# feelerBox1.net
KiCad netlist of a schematic drawn in EAGLE
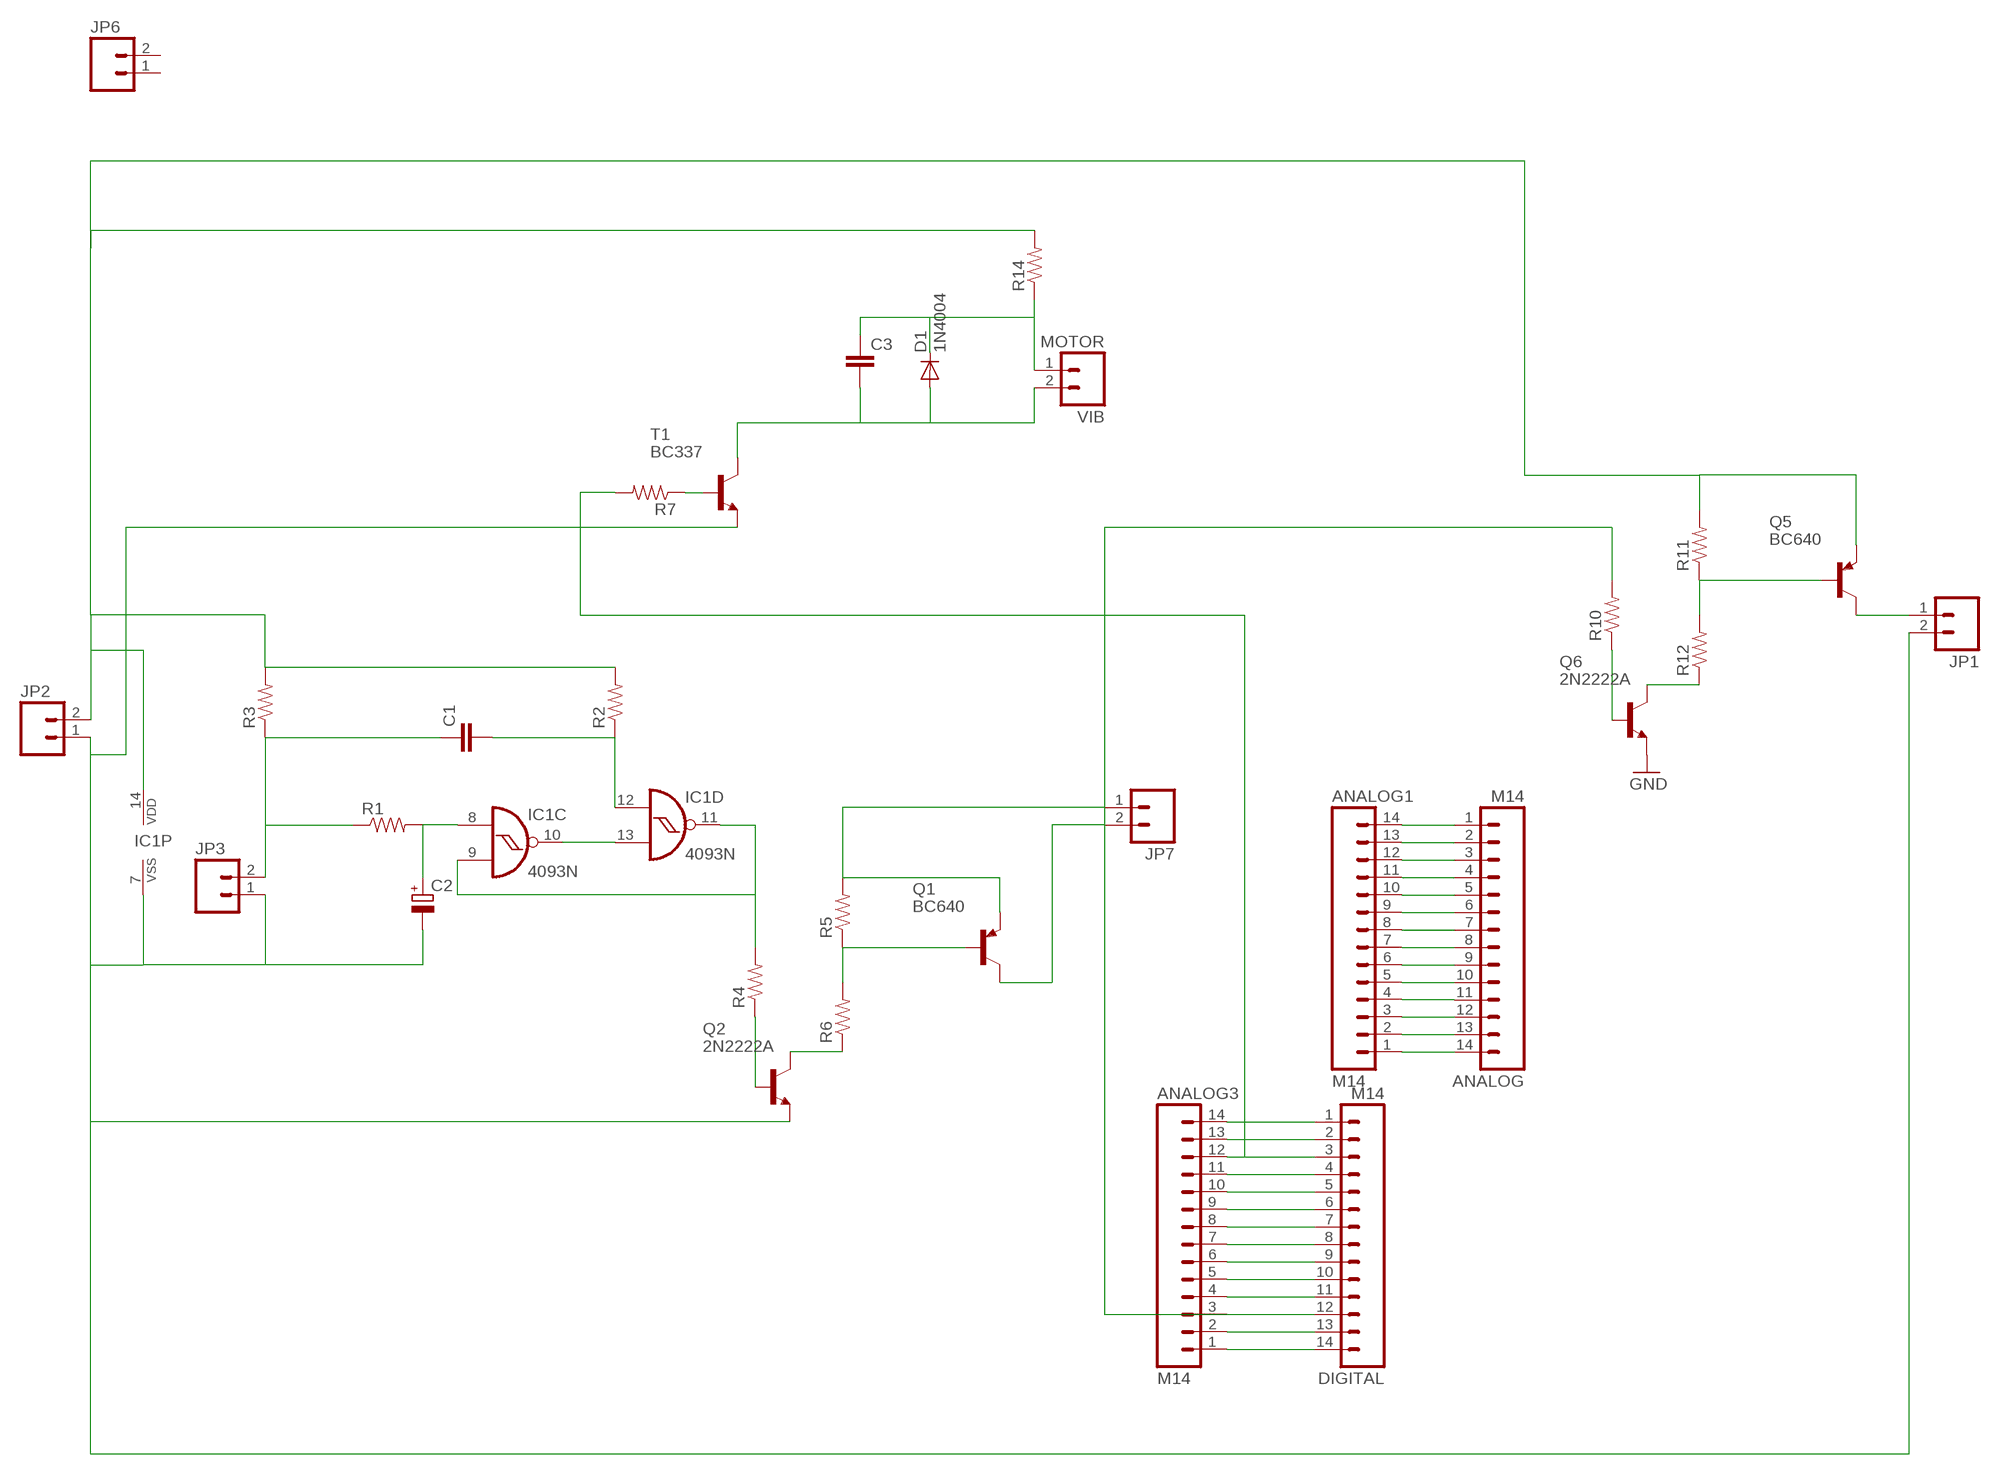
[diagram p0: schematic, sheet 1]

(export (version "E")
  (design (tool "Eeschema 10.0.6"))
  (components
    (comp (ref "ANALOG")
      (value "M14")
      (footprint "eagle-import:1X14")
      (libsource (lib "eagle-import") (part "M14"))
    )
    (comp (ref "ANALOG1")
      (value "M14")
      (footprint "eagle-import:1X14")
      (libsource (lib "eagle-import") (part "M14"))
    )
    (comp (ref "ANALOG3")
      (value "M14")
      (footprint "eagle-import:1X14")
      (libsource (lib "eagle-import") (part "M14"))
    )
    (comp (ref "C1")
      (value "0.1UF-50V-20%(PTH)KIT-EZ")
      (footprint "eagle-import:CAP-PTH-SMALL-KIT")
      (libsource (lib "eagle-import") (part "0.1UF-50V-20%(PTH)KIT-EZ"))
    )
    (comp (ref "C2")
      (value "CPOL-EUE2.5-5")
      (footprint "eagle-import:E2,5-5")
      (libsource (lib "eagle-import") (part "CPOL-EUE2.5-5"))
    )
    (comp (ref "C3")
      (value "CAPKIT")
      (footprint "eagle-import:CAP-PTH-SMALL-KIT")
      (libsource (lib "eagle-import") (part "CAPKIT"))
    )
    (comp (ref "D1")
      (value "1N4004")
      (footprint "eagle-import:DO41-10")
      (libsource (lib "eagle-import") (part "1N4004"))
    )
    (comp (ref "DIGITAL")
      (value "M14")
      (footprint "eagle-import:1X14")
      (libsource (lib "eagle-import") (part "M14"))
    )
    (comp (ref "IC1")
      (value "4093N")
      (footprint "eagle-import:DIL14")
      (libsource (lib "eagle-import") (part "4093N"))
    )
    (comp (ref "JP1")
      (value "M02PTH")
      (footprint "eagle-import:1X02")
      (libsource (lib "eagle-import") (part "M02PTH"))
    )
    (comp (ref "JP2")
      (value "M02PTH")
      (footprint "eagle-import:1X02")
      (libsource (lib "eagle-import") (part "M02PTH"))
    )
    (comp (ref "JP3")
      (value "M02PTH")
      (footprint "eagle-import:1X02")
      (libsource (lib "eagle-import") (part "M02PTH"))
    )
    (comp (ref "JP6")
      (value "M02PTH")
      (footprint "eagle-import:1X02")
      (libsource (lib "eagle-import") (part "M02PTH"))
    )
    (comp (ref "JP7")
      (value "M02PTH")
      (footprint "eagle-import:1X02")
      (libsource (lib "eagle-import") (part "M02PTH"))
    )
    (comp (ref "Q1")
      (value "BC640")
      (footprint "eagle-import:TO92-BCE")
      (libsource (lib "eagle-import") (part "BC640"))
    )
    (comp (ref "Q2")
      (value "2N2222A")
      (footprint "eagle-import:TO18")
      (libsource (lib "eagle-import") (part "2N2222A"))
    )
    (comp (ref "Q5")
      (value "BC640")
      (footprint "eagle-import:TO92-BCE")
      (libsource (lib "eagle-import") (part "BC640"))
    )
    (comp (ref "Q6")
      (value "2N2222A")
      (footprint "eagle-import:TO18")
      (libsource (lib "eagle-import") (part "2N2222A"))
    )
    (comp (ref "R1")
      (value "RESISTORAXIAL-0.3")
      (footprint "eagle-import:AXIAL-0.3")
      (libsource (lib "eagle-import") (part "RESISTORAXIAL-0.3"))
    )
    (comp (ref "R2")
      (value "RESISTORAXIAL-0.3")
      (footprint "eagle-import:AXIAL-0.3")
      (libsource (lib "eagle-import") (part "RESISTORAXIAL-0.3"))
    )
    (comp (ref "R3")
      (value "RESISTORAXIAL-0.3")
      (footprint "eagle-import:AXIAL-0.3")
      (libsource (lib "eagle-import") (part "RESISTORAXIAL-0.3"))
    )
    (comp (ref "R4")
      (value "RESISTORPTH-1/4W-VERT")
      (footprint "eagle-import:AXIAL-0.1")
      (libsource (lib "eagle-import") (part "RESISTORPTH-1/4W-VERT"))
    )
    (comp (ref "R5")
      (value "RESISTORPTH-1/4W-VERT")
      (footprint "eagle-import:AXIAL-0.1")
      (libsource (lib "eagle-import") (part "RESISTORPTH-1/4W-VERT"))
    )
    (comp (ref "R6")
      (value "RESISTORPTH-1/4W-VERT")
      (footprint "eagle-import:AXIAL-0.1")
      (libsource (lib "eagle-import") (part "RESISTORPTH-1/4W-VERT"))
    )
    (comp (ref "R7")
      (value "RESISTORAXIAL-0.3")
      (footprint "eagle-import:AXIAL-0.3")
      (libsource (lib "eagle-import") (part "RESISTORAXIAL-0.3"))
    )
    (comp (ref "R10")
      (value "RESISTORPTH-1/4W-VERT")
      (footprint "eagle-import:AXIAL-0.1")
      (libsource (lib "eagle-import") (part "RESISTORPTH-1/4W-VERT"))
    )
    (comp (ref "R11")
      (value "RESISTORPTH-1/4W-VERT")
      (footprint "eagle-import:AXIAL-0.1")
      (libsource (lib "eagle-import") (part "RESISTORPTH-1/4W-VERT"))
    )
    (comp (ref "R12")
      (value "RESISTORPTH-1/4W-VERT")
      (footprint "eagle-import:AXIAL-0.1")
      (libsource (lib "eagle-import") (part "RESISTORPTH-1/4W-VERT"))
    )
    (comp (ref "R14")
      (value "RESISTORPTH-1/4W-VERT")
      (footprint "eagle-import:AXIAL-0.1")
      (libsource (lib "eagle-import") (part "RESISTORPTH-1/4W-VERT"))
    )
    (comp (ref "T1")
      (value "BC337")
      (footprint "eagle-import:TO92")
      (libsource (lib "eagle-import") (part "BC337"))
    )
    (comp (ref "VIB")
      (value "MOTOR")
      (footprint "eagle-import:1X02")
      (libsource (lib "eagle-import") (part "M02PTH"))
    )
  )
  (nets
    (net (code "1") (name "GND") (class "Default")
      (node (ref "ANALOG3") (pin "13") (pinfunction "13_13") (pintype "passive"))
      (node (ref "DIGITAL") (pin "2") (pinfunction "2_2") (pintype "passive"))
      (node (ref "Q6") (pin "1") (pinfunction "E_1") (pintype "passive"))
    )
    (net (code "2") (name "Net-(ANALOG-Pad1)") (class "Default")
      (node (ref "ANALOG") (pin "1") (pinfunction "1_1") (pintype "passive"))
      (node (ref "ANALOG1") (pin "14") (pinfunction "14_14") (pintype "passive"))
    )
    (net (code "3") (name "Net-(ANALOG-Pad2)") (class "Default")
      (node (ref "ANALOG") (pin "2") (pinfunction "2_2") (pintype "passive"))
      (node (ref "ANALOG1") (pin "13") (pinfunction "13_13") (pintype "passive"))
    )
    (net (code "4") (name "Net-(ANALOG-Pad3)") (class "Default")
      (node (ref "ANALOG") (pin "3") (pinfunction "3_3") (pintype "passive"))
      (node (ref "ANALOG1") (pin "12") (pinfunction "12_12") (pintype "passive"))
    )
    (net (code "5") (name "Net-(ANALOG-Pad4)") (class "Default")
      (node (ref "ANALOG") (pin "4") (pinfunction "4_4") (pintype "passive"))
      (node (ref "ANALOG1") (pin "11") (pinfunction "11_11") (pintype "passive"))
    )
    (net (code "6") (name "Net-(ANALOG-Pad5)") (class "Default")
      (node (ref "ANALOG") (pin "5") (pinfunction "5_5") (pintype "passive"))
      (node (ref "ANALOG1") (pin "10") (pinfunction "10_10") (pintype "passive"))
    )
    (net (code "7") (name "Net-(ANALOG-Pad6)") (class "Default")
      (node (ref "ANALOG") (pin "6") (pinfunction "6_6") (pintype "passive"))
      (node (ref "ANALOG1") (pin "9") (pinfunction "9_9") (pintype "passive"))
    )
    (net (code "8") (name "Net-(ANALOG-Pad7)") (class "Default")
      (node (ref "ANALOG") (pin "7") (pinfunction "7_7") (pintype "passive"))
      (node (ref "ANALOG1") (pin "8") (pinfunction "8_8") (pintype "passive"))
    )
    (net (code "9") (name "Net-(ANALOG-Pad8)") (class "Default")
      (node (ref "ANALOG") (pin "8") (pinfunction "8_8") (pintype "passive"))
      (node (ref "ANALOG1") (pin "7") (pinfunction "7_7") (pintype "passive"))
    )
    (net (code "10") (name "Net-(ANALOG-Pad9)") (class "Default")
      (node (ref "ANALOG") (pin "9") (pinfunction "9_9") (pintype "passive"))
      (node (ref "ANALOG1") (pin "6") (pinfunction "6_6") (pintype "passive"))
    )
    (net (code "11") (name "Net-(ANALOG-Pad10)") (class "Default")
      (node (ref "ANALOG") (pin "10") (pinfunction "10_10") (pintype "passive"))
      (node (ref "ANALOG1") (pin "5") (pinfunction "5_5") (pintype "passive"))
    )
    (net (code "12") (name "Net-(ANALOG-Pad11)") (class "Default")
      (node (ref "ANALOG") (pin "11") (pinfunction "11_11") (pintype "passive"))
      (node (ref "ANALOG1") (pin "4") (pinfunction "4_4") (pintype "passive"))
    )
    (net (code "13") (name "Net-(ANALOG-Pad12)") (class "Default")
      (node (ref "ANALOG") (pin "12") (pinfunction "12_12") (pintype "passive"))
      (node (ref "ANALOG1") (pin "3") (pinfunction "3_3") (pintype "passive"))
    )
    (net (code "14") (name "Net-(ANALOG-Pad13)") (class "Default")
      (node (ref "ANALOG") (pin "13") (pinfunction "13_13") (pintype "passive"))
      (node (ref "ANALOG1") (pin "2") (pinfunction "2_2") (pintype "passive"))
    )
    (net (code "15") (name "Net-(ANALOG-Pad14)") (class "Default")
      (node (ref "ANALOG") (pin "14") (pinfunction "14_14") (pintype "passive"))
      (node (ref "ANALOG1") (pin "1") (pinfunction "1_1") (pintype "passive"))
    )
    (net (code "16") (name "Net-(ANALOG3-Pad1)") (class "Default")
      (node (ref "ANALOG3") (pin "1") (pinfunction "1_1") (pintype "passive"))
      (node (ref "DIGITAL") (pin "14") (pinfunction "14_14") (pintype "passive"))
    )
    (net (code "17") (name "Net-(ANALOG3-Pad2)") (class "Default")
      (node (ref "ANALOG3") (pin "2") (pinfunction "2_2") (pintype "passive"))
      (node (ref "DIGITAL") (pin "13") (pinfunction "13_13") (pintype "passive"))
    )
    (net (code "18") (name "Net-(ANALOG3-Pad4)") (class "Default")
      (node (ref "ANALOG3") (pin "4") (pinfunction "4_4") (pintype "passive"))
      (node (ref "DIGITAL") (pin "11") (pinfunction "11_11") (pintype "passive"))
    )
    (net (code "19") (name "Net-(ANALOG3-Pad5)") (class "Default")
      (node (ref "ANALOG3") (pin "5") (pinfunction "5_5") (pintype "passive"))
      (node (ref "DIGITAL") (pin "10") (pinfunction "10_10") (pintype "passive"))
    )
    (net (code "20") (name "Net-(ANALOG3-Pad6)") (class "Default")
      (node (ref "ANALOG3") (pin "6") (pinfunction "6_6") (pintype "passive"))
      (node (ref "DIGITAL") (pin "9") (pinfunction "9_9") (pintype "passive"))
    )
    (net (code "21") (name "Net-(ANALOG3-Pad7)") (class "Default")
      (node (ref "ANALOG3") (pin "7") (pinfunction "7_7") (pintype "passive"))
      (node (ref "DIGITAL") (pin "8") (pinfunction "8_8") (pintype "passive"))
    )
    (net (code "22") (name "Net-(ANALOG3-Pad8)") (class "Default")
      (node (ref "ANALOG3") (pin "8") (pinfunction "8_8") (pintype "passive"))
      (node (ref "DIGITAL") (pin "7") (pinfunction "7_7") (pintype "passive"))
    )
    (net (code "23") (name "Net-(ANALOG3-Pad9)") (class "Default")
      (node (ref "ANALOG3") (pin "9") (pinfunction "9_9") (pintype "passive"))
      (node (ref "DIGITAL") (pin "6") (pinfunction "6_6") (pintype "passive"))
    )
    (net (code "24") (name "Net-(ANALOG3-Pad10)") (class "Default")
      (node (ref "ANALOG3") (pin "10") (pinfunction "10_10") (pintype "passive"))
      (node (ref "DIGITAL") (pin "5") (pinfunction "5_5") (pintype "passive"))
    )
    (net (code "25") (name "Net-(ANALOG3-Pad11)") (class "Default")
      (node (ref "ANALOG3") (pin "11") (pinfunction "11_11") (pintype "passive"))
      (node (ref "DIGITAL") (pin "4") (pinfunction "4_4") (pintype "passive"))
    )
    (net (code "26") (name "Net-(ANALOG3-Pad14)") (class "Default")
      (node (ref "ANALOG3") (pin "14") (pinfunction "14_14") (pintype "passive"))
      (node (ref "DIGITAL") (pin "1") (pinfunction "1_1") (pintype "passive"))
    )
    (net (code "27") (name "Net-(IC1C-I0)") (class "Default")
      (node (ref "C2") (pin "+") (pinfunction "+_+") (pintype "passive"))
      (node (ref "IC1") (pin "8") (pinfunction "I0_8") (pintype "input"))
      (node (ref "R1") (pin "P$2") (pinfunction "2_P$2") (pintype "passive"))
    )
    (net (code "28") (name "Net-(IC1C-I1)") (class "Default")
      (node (ref "IC1") (pin "11") (pinfunction "O_11") (pintype "output"))
      (node (ref "IC1") (pin "9") (pinfunction "I1_9") (pintype "input"))
      (node (ref "R4") (pin "P$2") (pinfunction "2_P$2") (pintype "passive"))
    )
    (net (code "29") (name "Net-(IC1C-O)") (class "Default")
      (node (ref "IC1") (pin "10") (pinfunction "O_10") (pintype "output"))
      (node (ref "IC1") (pin "13") (pinfunction "I1_13") (pintype "input"))
    )
    (net (code "30") (name "Net-(IC1D-I0)") (class "Default")
      (node (ref "C1") (pin "2") (pinfunction "2_2") (pintype "passive"))
      (node (ref "IC1") (pin "12") (pinfunction "I0_12") (pintype "input"))
      (node (ref "R2") (pin "P$1") (pinfunction "1_P$1") (pintype "passive"))
    )
    (net (code "31") (name "Net-(IC1E-VDD)") (class "Default")
      (node (ref "IC1") (pin "14") (pinfunction "VDD_14") (pintype "power_in"))
      (node (ref "JP2") (pin "2") (pinfunction "2_2") (pintype "passive"))
      (node (ref "Q5") (pin "E") (pinfunction "E_E") (pintype "passive"))
      (node (ref "R11") (pin "P$2") (pinfunction "2_P$2") (pintype "passive"))
      (node (ref "R14") (pin "P$2") (pinfunction "2_P$2") (pintype "passive"))
      (node (ref "R2") (pin "P$2") (pinfunction "2_P$2") (pintype "passive"))
      (node (ref "R3") (pin "P$2") (pinfunction "2_P$2") (pintype "passive"))
    )
    (net (code "32") (name "Net-(IC1E-VSS)") (class "Default")
      (node (ref "C2") (pin "-") (pinfunction "-_-") (pintype "passive"))
      (node (ref "IC1") (pin "7") (pinfunction "VSS_7") (pintype "power_in"))
      (node (ref "JP1") (pin "2") (pinfunction "2_2") (pintype "passive"))
      (node (ref "JP2") (pin "1") (pinfunction "1_1") (pintype "passive"))
      (node (ref "JP3") (pin "1") (pinfunction "1_1") (pintype "passive"))
      (node (ref "Q2") (pin "1") (pinfunction "E_1") (pintype "passive"))
      (node (ref "T1") (pin "1") (pinfunction "E_1") (pintype "passive"))
    )
    (net (code "33") (name "Net-(JP1-Pad1)") (class "Default")
      (node (ref "JP1") (pin "1") (pinfunction "1_1") (pintype "passive"))
      (node (ref "Q5") (pin "C") (pinfunction "C_C") (pintype "passive"))
    )
    (net (code "34") (name "Net-(JP7-Pad2)") (class "Default")
      (node (ref "JP7") (pin "2") (pinfunction "2_2") (pintype "passive"))
      (node (ref "Q1") (pin "C") (pinfunction "C_C") (pintype "passive"))
    )
    (net (code "35") (name "Net-(Q2-B)") (class "Default")
      (node (ref "Q2") (pin "2") (pinfunction "B_2") (pintype "passive"))
      (node (ref "R4") (pin "P$1") (pinfunction "1_P$1") (pintype "passive"))
    )
    (net (code "36") (name "Net-(Q2-C)") (class "Default")
      (node (ref "Q2") (pin "3") (pinfunction "C_3") (pintype "passive"))
      (node (ref "R6") (pin "P$1") (pinfunction "1_P$1") (pintype "passive"))
    )
    (net (code "37") (name "Net-(Q6-B)") (class "Default")
      (node (ref "Q6") (pin "2") (pinfunction "B_2") (pintype "passive"))
      (node (ref "R10") (pin "P$1") (pinfunction "1_P$1") (pintype "passive"))
    )
    (net (code "38") (name "Net-(Q6-C)") (class "Default")
      (node (ref "Q6") (pin "3") (pinfunction "C_3") (pintype "passive"))
      (node (ref "R12") (pin "P$1") (pinfunction "1_P$1") (pintype "passive"))
    )
    (net (code "39") (name "Net-(R1-1)") (class "Default")
      (node (ref "C1") (pin "1") (pinfunction "1_1") (pintype "passive"))
      (node (ref "JP3") (pin "2") (pinfunction "2_2") (pintype "passive"))
      (node (ref "R1") (pin "P$1") (pinfunction "1_P$1") (pintype "passive"))
      (node (ref "R3") (pin "P$1") (pinfunction "1_P$1") (pintype "passive"))
    )
    (net (code "40") (name "Net-(R5-1)") (class "Default")
      (node (ref "Q1") (pin "B") (pinfunction "B_B") (pintype "passive"))
      (node (ref "R5") (pin "P$1") (pinfunction "1_P$1") (pintype "passive"))
      (node (ref "R6") (pin "P$2") (pinfunction "2_P$2") (pintype "passive"))
    )
    (net (code "41") (name "Net-(R5-2)") (class "Default")
      (node (ref "JP7") (pin "1") (pinfunction "1_1") (pintype "passive"))
      (node (ref "Q1") (pin "E") (pinfunction "E_E") (pintype "passive"))
      (node (ref "R5") (pin "P$2") (pinfunction "2_P$2") (pintype "passive"))
    )
    (net (code "42") (name "Net-(R7-1)") (class "Default")
      (node (ref "R7") (pin "P$1") (pinfunction "1_P$1") (pintype "passive"))
      (node (ref "T1") (pin "2") (pinfunction "B_2") (pintype "passive"))
    )
    (net (code "43") (name "Net-(R7-2)") (class "Default")
      (node (ref "ANALOG3") (pin "12") (pinfunction "12_12") (pintype "passive"))
      (node (ref "DIGITAL") (pin "3") (pinfunction "3_3") (pintype "passive"))
      (node (ref "R7") (pin "P$2") (pinfunction "2_P$2") (pintype "passive"))
    )
    (net (code "44") (name "Net-(R10-2)") (class "Default")
      (node (ref "ANALOG3") (pin "3") (pinfunction "3_3") (pintype "passive"))
      (node (ref "DIGITAL") (pin "12") (pinfunction "12_12") (pintype "passive"))
      (node (ref "R10") (pin "P$2") (pinfunction "2_P$2") (pintype "passive"))
    )
    (net (code "45") (name "Net-(R11-1)") (class "Default")
      (node (ref "Q5") (pin "B") (pinfunction "B_B") (pintype "passive"))
      (node (ref "R11") (pin "P$1") (pinfunction "1_P$1") (pintype "passive"))
      (node (ref "R12") (pin "P$2") (pinfunction "2_P$2") (pintype "passive"))
    )
    (net (code "46") (name "Net-(R14-1)") (class "Default")
      (node (ref "C3") (pin "1") (pinfunction "1_1") (pintype "passive"))
      (node (ref "D1") (pin "C") (pinfunction "C_C") (pintype "passive"))
      (node (ref "R14") (pin "P$1") (pinfunction "1_P$1") (pintype "passive"))
      (node (ref "VIB") (pin "1") (pinfunction "1_1") (pintype "passive"))
    )
    (net (code "47") (name "Net-(T1-C)") (class "Default")
      (node (ref "C3") (pin "2") (pinfunction "2_2") (pintype "passive"))
      (node (ref "D1") (pin "A") (pinfunction "A_A") (pintype "passive"))
      (node (ref "T1") (pin "3") (pinfunction "C_3") (pintype "passive"))
      (node (ref "VIB") (pin "2") (pinfunction "2_2") (pintype "passive"))
    )
    (net (code "48") (name "unconnected-(JP6-Pad1)") (class "Default")
      (node (ref "JP6") (pin "1") (pinfunction "1_1") (pintype "passive"))
    )
    (net (code "49") (name "unconnected-(JP6-Pad2)") (class "Default")
      (node (ref "JP6") (pin "2") (pinfunction "2_2") (pintype "passive"))
    )
  )
)
